# mainboard.net
KiCad netlist of a schematic drawn in EAGLE
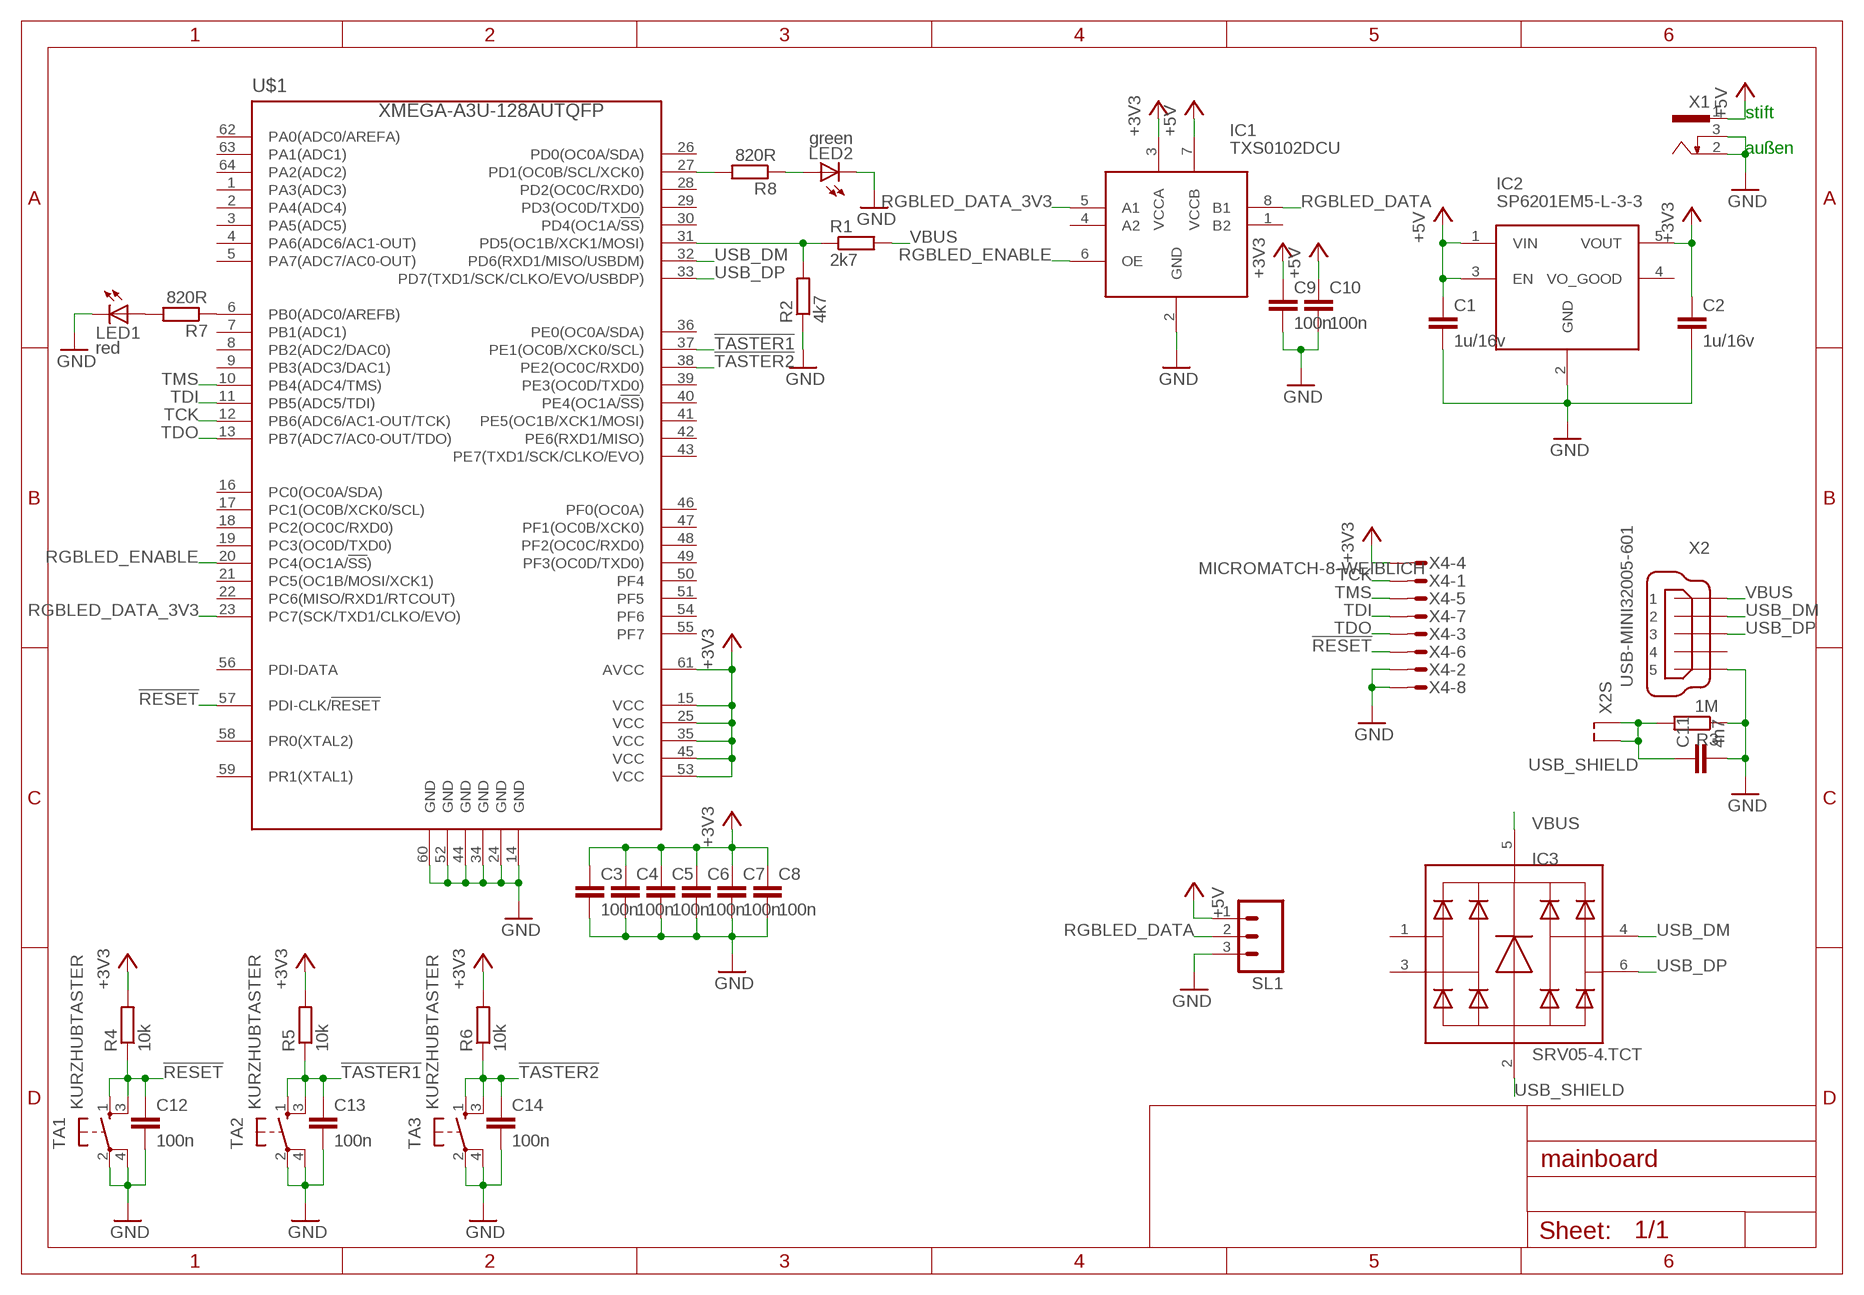
[diagram p0: schematic, sheet 1]

(export (version "E")
  (design (tool "Eeschema 10.0.6"))
  (components
    (comp (ref "C1")
      (value "1u/16v")
      (footprint "eagle-import:C0603")
      (libsource (lib "eagle-import") (part "C-EUC0603"))
    )
    (comp (ref "C2")
      (value "1u/16v")
      (footprint "eagle-import:C0603")
      (libsource (lib "eagle-import") (part "C-EUC0603"))
    )
    (comp (ref "C3")
      (value "100n")
      (footprint "eagle-import:C0603")
      (libsource (lib "eagle-import") (part "C-EUC0603"))
    )
    (comp (ref "C4")
      (value "100n")
      (footprint "eagle-import:C0603")
      (libsource (lib "eagle-import") (part "C-EUC0603"))
    )
    (comp (ref "C5")
      (value "100n")
      (footprint "eagle-import:C0603")
      (libsource (lib "eagle-import") (part "C-EUC0603"))
    )
    (comp (ref "C6")
      (value "100n")
      (footprint "eagle-import:C0603")
      (libsource (lib "eagle-import") (part "C-EUC0603"))
    )
    (comp (ref "C7")
      (value "100n")
      (footprint "eagle-import:C0603")
      (libsource (lib "eagle-import") (part "C-EUC0603"))
    )
    (comp (ref "C8")
      (value "100n")
      (footprint "eagle-import:C0603")
      (libsource (lib "eagle-import") (part "C-EUC0603"))
    )
    (comp (ref "C9")
      (value "100n")
      (footprint "eagle-import:C0603")
      (libsource (lib "eagle-import") (part "C-EUC0603"))
    )
    (comp (ref "C10")
      (value "100n")
      (footprint "eagle-import:C0603")
      (libsource (lib "eagle-import") (part "C-EUC0603"))
    )
    (comp (ref "C11")
      (value "4n7")
      (footprint "eagle-import:C0603")
      (libsource (lib "eagle-import") (part "C-EUC0603"))
    )
    (comp (ref "C12")
      (value "100n")
      (footprint "eagle-import:C0603")
      (libsource (lib "eagle-import") (part "C-EUC0603"))
    )
    (comp (ref "C13")
      (value "100n")
      (footprint "eagle-import:C0603")
      (libsource (lib "eagle-import") (part "C-EUC0603"))
    )
    (comp (ref "C14")
      (value "100n")
      (footprint "eagle-import:C0603")
      (libsource (lib "eagle-import") (part "C-EUC0603"))
    )
    (comp (ref "IC1")
      (value "TXS0102DCU")
      (footprint "eagle-import:DCU8")
      (libsource (lib "eagle-import") (part "TXS0102DCU"))
    )
    (comp (ref "IC2")
      (value "SP6201EM5-L-3-3")
      (footprint "eagle-import:SOT23-5")
      (libsource (lib "eagle-import") (part "SP6201EM5-L-3-3"))
    )
    (comp (ref "IC3")
      (value "SRV05-4.TCT")
      (footprint "eagle-import:SOT23-6")
      (libsource (lib "eagle-import") (part "SRV05-4.TCT"))
    )
    (comp (ref "LED1")
      (value "red")
      (footprint "eagle-import:CHIPLED_0603")
      (libsource (lib "eagle-import") (part "LEDCHIPLED_0603LR"))
    )
    (comp (ref "LED2")
      (value "green")
      (footprint "eagle-import:CHIPLED_0603")
      (libsource (lib "eagle-import") (part "LEDCHIPLED_0603LG"))
    )
    (comp (ref "R1")
      (value "2k7")
      (footprint "eagle-import:R0603")
      (libsource (lib "eagle-import") (part "R-EU_R0603"))
    )
    (comp (ref "R2")
      (value "4k7")
      (footprint "eagle-import:R0603")
      (libsource (lib "eagle-import") (part "R-EU_R0603"))
    )
    (comp (ref "R3")
      (value "1M")
      (footprint "eagle-import:R0603")
      (libsource (lib "eagle-import") (part "R-EU_R0603"))
    )
    (comp (ref "R4")
      (value "10k")
      (footprint "eagle-import:R0603")
      (libsource (lib "eagle-import") (part "R-EU_R0603"))
    )
    (comp (ref "R5")
      (value "10k")
      (footprint "eagle-import:R0603")
      (libsource (lib "eagle-import") (part "R-EU_R0603"))
    )
    (comp (ref "R6")
      (value "10k")
      (footprint "eagle-import:R0603")
      (libsource (lib "eagle-import") (part "R-EU_R0603"))
    )
    (comp (ref "R7")
      (value "820R")
      (footprint "eagle-import:R0603")
      (libsource (lib "eagle-import") (part "R-EU_R0603"))
    )
    (comp (ref "R8")
      (value "820R")
      (footprint "eagle-import:R0603")
      (libsource (lib "eagle-import") (part "R-EU_R0603"))
    )
    (comp (ref "SL1")
      (value "M03")
      (footprint "eagle-import:03P")
      (libsource (lib "eagle-import") (part "M03"))
    )
    (comp (ref "TA1")
      (value "KURZHUBTASTER")
      (footprint "eagle-import:TA93XX")
      (libsource (lib "eagle-import") (part "KURZHUBTASTER"))
    )
    (comp (ref "TA2")
      (value "KURZHUBTASTER")
      (footprint "eagle-import:TA93XX")
      (libsource (lib "eagle-import") (part "KURZHUBTASTER"))
    )
    (comp (ref "TA3")
      (value "KURZHUBTASTER")
      (footprint "eagle-import:TA93XX")
      (libsource (lib "eagle-import") (part "KURZHUBTASTER"))
    )
    (comp (ref "U$1")
      (value "XMEGA-A3U-128AUTQFP")
      (footprint "eagle-import:TQFP64")
      (libsource (lib "eagle-import") (part "XMEGA-A3UTQFP-128AU"))
    )
    (comp (ref "X1")
      (value "733980-62")
      (footprint "eagle-import:733980-62")
      (libsource (lib "eagle-import") (part "73398?0-62"))
    )
    (comp (ref "X2")
      (value "USB-MINI32005-601")
      (footprint "eagle-import:32005-601")
      (libsource (lib "eagle-import") (part "USB-MINI32005-601"))
    )
    (comp (ref "X4")
      (value "MICROMATCH-8-WEIBLICH")
      (footprint "eagle-import:MICROMATCH-8")
      (libsource (lib "eagle-import") (part "MICROMATCH-8-WEIBLICH"))
    )
  )
  (nets
    (net (code "1") (name "+3V3") (class "Default")
      (node (ref "C2") (pin "1") (pinfunction "1_1") (pintype "passive"))
      (node (ref "C3") (pin "1") (pinfunction "1_1") (pintype "passive"))
      (node (ref "C4") (pin "1") (pinfunction "1_1") (pintype "passive"))
      (node (ref "C5") (pin "1") (pinfunction "1_1") (pintype "passive"))
      (node (ref "C6") (pin "1") (pinfunction "1_1") (pintype "passive"))
      (node (ref "C7") (pin "1") (pinfunction "1_1") (pintype "passive"))
      (node (ref "C8") (pin "1") (pinfunction "1_1") (pintype "passive"))
      (node (ref "C9") (pin "1") (pinfunction "1_1") (pintype "passive"))
      (node (ref "IC1") (pin "3") (pinfunction "VCCA_3") (pintype "power_in"))
      (node (ref "IC2") (pin "5") (pinfunction "VOUT_5") (pintype "power_in"))
      (node (ref "R4") (pin "2") (pinfunction "2_2") (pintype "passive"))
      (node (ref "R5") (pin "2") (pinfunction "2_2") (pintype "passive"))
      (node (ref "R6") (pin "2") (pinfunction "2_2") (pintype "passive"))
      (node (ref "U$1") (pin "15") (pinfunction "VCC_15") (pintype "power_in"))
      (node (ref "U$1") (pin "25") (pinfunction "VCC_25") (pintype "power_in"))
      (node (ref "U$1") (pin "35") (pinfunction "VCC_35") (pintype "power_in"))
      (node (ref "U$1") (pin "45") (pinfunction "VCC_45") (pintype "power_in"))
      (node (ref "U$1") (pin "53") (pinfunction "VCC_53") (pintype "power_in"))
      (node (ref "U$1") (pin "61") (pinfunction "AVCC_61") (pintype "power_in"))
      (node (ref "X4") (pin "4") (pinfunction "S_4") (pintype "passive"))
    )
    (net (code "2") (name "+5V") (class "Default")
      (node (ref "C1") (pin "1") (pinfunction "1_1") (pintype "passive"))
      (node (ref "C10") (pin "1") (pinfunction "1_1") (pintype "passive"))
      (node (ref "IC1") (pin "7") (pinfunction "VCCB_7") (pintype "power_in"))
      (node (ref "IC2") (pin "1") (pinfunction "VIN_1") (pintype "power_in"))
      (node (ref "IC2") (pin "3") (pinfunction "EN_3") (pintype "input"))
      (node (ref "SL1") (pin "1") (pinfunction "1_1") (pintype "passive"))
      (node (ref "X1") (pin "1") (pinfunction "1_1") (pintype "passive"))
    )
    (net (code "3") (name "/RGBLED_DATA") (class "Default")
      (node (ref "IC1") (pin "8") (pinfunction "B1_8") (pintype "bidirectional"))
      (node (ref "SL1") (pin "2") (pinfunction "2_2") (pintype "passive"))
    )
    (net (code "4") (name "/RGBLED_DATA_3V3") (class "Default")
      (node (ref "IC1") (pin "5") (pinfunction "A1_5") (pintype "bidirectional"))
      (node (ref "U$1") (pin "23") (pinfunction "PC7(SCK/TXD1/CLKO/EVO)_23") (pintype "bidirectional"))
    )
    (net (code "5") (name "/RGBLED_ENABLE") (class "Default")
      (node (ref "IC1") (pin "6") (pinfunction "OE_6") (pintype "input"))
      (node (ref "U$1") (pin "20") (pinfunction "PC4(OC1A/~{SS})_20") (pintype "bidirectional"))
    )
    (net (code "6") (name "/TCK") (class "Default")
      (node (ref "U$1") (pin "12") (pinfunction "PB6(ADC6/AC1-OUT/TCK)_12") (pintype "bidirectional"))
      (node (ref "X4") (pin "1") (pinfunction "S_1") (pintype "passive"))
    )
    (net (code "7") (name "/TDI") (class "Default")
      (node (ref "U$1") (pin "11") (pinfunction "PB5(ADC5/TDI)_11") (pintype "bidirectional"))
      (node (ref "X4") (pin "7") (pinfunction "S_7") (pintype "passive"))
    )
    (net (code "8") (name "/TDO") (class "Default")
      (node (ref "U$1") (pin "13") (pinfunction "PB7(ADC7/AC0-OUT/TDO)_13") (pintype "bidirectional"))
      (node (ref "X4") (pin "3") (pinfunction "S_3") (pintype "passive"))
    )
    (net (code "9") (name "/TMS") (class "Default")
      (node (ref "U$1") (pin "10") (pinfunction "PB4(ADC4/TMS)_10") (pintype "bidirectional"))
      (node (ref "X4") (pin "5") (pinfunction "S_5") (pintype "passive"))
    )
    (net (code "10") (name "/USB_DM") (class "Default")
      (node (ref "IC3") (pin "4") (pinfunction "3_4") (pintype "passive"))
      (node (ref "U$1") (pin "32") (pinfunction "PD6(RXD1/MISO/USBDM)_32") (pintype "bidirectional"))
      (node (ref "X2") (pin "2") (pinfunction "2_2") (pintype "passive"))
    )
    (net (code "11") (name "/USB_DP") (class "Default")
      (node (ref "IC3") (pin "6") (pinfunction "4_6") (pintype "passive"))
      (node (ref "U$1") (pin "33") (pinfunction "PD7(TXD1/SCK/CLKO/EVO/USBDP)_33") (pintype "bidirectional"))
      (node (ref "X2") (pin "3") (pinfunction "3_3") (pintype "passive"))
    )
    (net (code "12") (name "/USB_SHIELD") (class "Default")
      (node (ref "C11") (pin "1") (pinfunction "1_1") (pintype "passive"))
      (node (ref "IC3") (pin "2") (pinfunction "A_2") (pintype "passive"))
      (node (ref "R3") (pin "2") (pinfunction "2_2") (pintype "passive"))
      (node (ref "X2") (pin "M1") (pinfunction "S1_M1") (pintype "passive"))
      (node (ref "X2") (pin "M2") (pinfunction "S2_M2") (pintype "passive"))
    )
    (net (code "13") (name "/VBUS") (class "Default")
      (node (ref "IC3") (pin "5") (pinfunction "K_5") (pintype "passive"))
      (node (ref "R1") (pin "2") (pinfunction "2_2") (pintype "passive"))
      (node (ref "X2") (pin "1") (pinfunction "1_1") (pintype "passive"))
    )
    (net (code "14") (name "/~{RESET}") (class "Default")
      (node (ref "C12") (pin "1") (pinfunction "1_1") (pintype "passive"))
      (node (ref "R4") (pin "1") (pinfunction "1_1") (pintype "passive"))
      (node (ref "TA1") (pin "1") (pinfunction "S_1") (pintype "passive"))
      (node (ref "TA1") (pin "3") (pinfunction "S1_3") (pintype "passive"))
      (node (ref "U$1") (pin "57") (pinfunction "PDI-CLK/~{RESET}_57") (pintype "input"))
      (node (ref "X4") (pin "6") (pinfunction "S_6") (pintype "passive"))
    )
    (net (code "15") (name "/~{TASTER1}") (class "Default")
      (node (ref "C13") (pin "1") (pinfunction "1_1") (pintype "passive"))
      (node (ref "R5") (pin "1") (pinfunction "1_1") (pintype "passive"))
      (node (ref "TA2") (pin "1") (pinfunction "S_1") (pintype "passive"))
      (node (ref "TA2") (pin "3") (pinfunction "S1_3") (pintype "passive"))
      (node (ref "U$1") (pin "37") (pinfunction "PE1(OC0B/XCK0/SCL)_37") (pintype "bidirectional"))
    )
    (net (code "16") (name "/~{TASTER2}") (class "Default")
      (node (ref "C14") (pin "1") (pinfunction "1_1") (pintype "passive"))
      (node (ref "R6") (pin "1") (pinfunction "1_1") (pintype "passive"))
      (node (ref "TA3") (pin "1") (pinfunction "S_1") (pintype "passive"))
      (node (ref "TA3") (pin "3") (pinfunction "S1_3") (pintype "passive"))
      (node (ref "U$1") (pin "38") (pinfunction "PE2(OC0C/RXD0)_38") (pintype "bidirectional"))
    )
    (net (code "17") (name "GND") (class "Default")
      (node (ref "C1") (pin "2") (pinfunction "2_2") (pintype "passive"))
      (node (ref "C10") (pin "2") (pinfunction "2_2") (pintype "passive"))
      (node (ref "C11") (pin "2") (pinfunction "2_2") (pintype "passive"))
      (node (ref "C12") (pin "2") (pinfunction "2_2") (pintype "passive"))
      (node (ref "C13") (pin "2") (pinfunction "2_2") (pintype "passive"))
      (node (ref "C14") (pin "2") (pinfunction "2_2") (pintype "passive"))
      (node (ref "C2") (pin "2") (pinfunction "2_2") (pintype "passive"))
      (node (ref "C3") (pin "2") (pinfunction "2_2") (pintype "passive"))
      (node (ref "C4") (pin "2") (pinfunction "2_2") (pintype "passive"))
      (node (ref "C5") (pin "2") (pinfunction "2_2") (pintype "passive"))
      (node (ref "C6") (pin "2") (pinfunction "2_2") (pintype "passive"))
      (node (ref "C7") (pin "2") (pinfunction "2_2") (pintype "passive"))
      (node (ref "C8") (pin "2") (pinfunction "2_2") (pintype "passive"))
      (node (ref "C9") (pin "2") (pinfunction "2_2") (pintype "passive"))
      (node (ref "IC1") (pin "2") (pinfunction "GND_2") (pintype "power_in"))
      (node (ref "IC2") (pin "2") (pinfunction "GND_2") (pintype "power_in"))
      (node (ref "LED1") (pin "C") (pinfunction "C_C") (pintype "passive"))
      (node (ref "LED2") (pin "C") (pinfunction "C_C") (pintype "passive"))
      (node (ref "R2") (pin "1") (pinfunction "1_1") (pintype "passive"))
      (node (ref "R3") (pin "1") (pinfunction "1_1") (pintype "passive"))
      (node (ref "SL1") (pin "3") (pinfunction "3_3") (pintype "passive"))
      (node (ref "TA1") (pin "2") (pinfunction "P_2") (pintype "passive"))
      (node (ref "TA1") (pin "4") (pinfunction "P1_4") (pintype "passive"))
      (node (ref "TA2") (pin "2") (pinfunction "P_2") (pintype "passive"))
      (node (ref "TA2") (pin "4") (pinfunction "P1_4") (pintype "passive"))
      (node (ref "TA3") (pin "2") (pinfunction "P_2") (pintype "passive"))
      (node (ref "TA3") (pin "4") (pinfunction "P1_4") (pintype "passive"))
      (node (ref "U$1") (pin "14") (pinfunction "GND_14") (pintype "power_in"))
      (node (ref "U$1") (pin "24") (pinfunction "GND_24") (pintype "power_in"))
      (node (ref "U$1") (pin "34") (pinfunction "GND_34") (pintype "power_in"))
      (node (ref "U$1") (pin "44") (pinfunction "GND_44") (pintype "power_in"))
      (node (ref "U$1") (pin "52") (pinfunction "GND_52") (pintype "power_in"))
      (node (ref "U$1") (pin "60") (pinfunction "GND_60") (pintype "power_in"))
      (node (ref "X1") (pin "2") (pinfunction "2_2") (pintype "passive"))
      (node (ref "X1") (pin "3") (pinfunction "3_3") (pintype "passive"))
      (node (ref "X2") (pin "5") (pinfunction "5_5") (pintype "passive"))
      (node (ref "X4") (pin "2") (pinfunction "S_2") (pintype "passive"))
      (node (ref "X4") (pin "8") (pinfunction "S_8") (pintype "passive"))
    )
    (net (code "18") (name "Net-(LED1-PadA)") (class "Default")
      (node (ref "LED1") (pin "A") (pinfunction "A_A") (pintype "passive"))
      (node (ref "R7") (pin "2") (pinfunction "2_2") (pintype "passive"))
    )
    (net (code "19") (name "Net-(LED2-PadA)") (class "Default")
      (node (ref "LED2") (pin "A") (pinfunction "A_A") (pintype "passive"))
      (node (ref "R8") (pin "1") (pinfunction "1_1") (pintype "passive"))
    )
    (net (code "20") (name "Net-(U$1-PB0(ADC0{slash}AREFB))") (class "Default")
      (node (ref "R7") (pin "1") (pinfunction "1_1") (pintype "passive"))
      (node (ref "U$1") (pin "6") (pinfunction "PB0(ADC0/AREFB)_6") (pintype "bidirectional"))
    )
    (net (code "21") (name "Net-(U$1-PD1(OC0B{slash}SCL{slash}XCK0))") (class "Default")
      (node (ref "R8") (pin "2") (pinfunction "2_2") (pintype "passive"))
      (node (ref "U$1") (pin "27") (pinfunction "PD1(OC0B/SCL/XCK0)_27") (pintype "bidirectional"))
    )
    (net (code "22") (name "Net-(U$1-PD5(OC1B{slash}XCK1{slash}MOSI))") (class "Default")
      (node (ref "R1") (pin "1") (pinfunction "1_1") (pintype "passive"))
      (node (ref "R2") (pin "2") (pinfunction "2_2") (pintype "passive"))
      (node (ref "U$1") (pin "31") (pinfunction "PD5(OC1B/XCK1/MOSI)_31") (pintype "bidirectional"))
    )
    (net (code "23") (name "unconnected-(IC1-A2-Pad4)") (class "Default")
      (node (ref "IC1") (pin "4") (pinfunction "A2_4") (pintype "bidirectional"))
    )
    (net (code "24") (name "unconnected-(IC1-B2-Pad1)") (class "Default")
      (node (ref "IC1") (pin "1") (pinfunction "B2_1") (pintype "bidirectional"))
    )
    (net (code "25") (name "unconnected-(IC2-VO_GOOD-Pad4)") (class "Default")
      (node (ref "IC2") (pin "4") (pinfunction "VO_GOOD_4") (pintype "output"))
    )
    (net (code "26") (name "unconnected-(IC3-2-Pad3)") (class "Default")
      (node (ref "IC3") (pin "3") (pinfunction "2_3") (pintype "passive"))
    )
    (net (code "27") (name "unconnected-(IC3-Pad1)") (class "Default")
      (node (ref "IC3") (pin "1") (pinfunction "1_1") (pintype "passive"))
    )
    (net (code "28") (name "unconnected-(U$1-PA0(ADC0{slash}AREFA)-Pad62)") (class "Default")
      (node (ref "U$1") (pin "62") (pinfunction "PA0(ADC0/AREFA)_62") (pintype "bidirectional"))
    )
    (net (code "29") (name "unconnected-(U$1-PA1(ADC1)-Pad63)") (class "Default")
      (node (ref "U$1") (pin "63") (pinfunction "PA1(ADC1)_63") (pintype "bidirectional"))
    )
    (net (code "30") (name "unconnected-(U$1-PA2(ADC2)-Pad64)") (class "Default")
      (node (ref "U$1") (pin "64") (pinfunction "PA2(ADC2)_64") (pintype "bidirectional"))
    )
    (net (code "31") (name "unconnected-(U$1-PA3(ADC3)-Pad1)") (class "Default")
      (node (ref "U$1") (pin "1") (pinfunction "PA3(ADC3)_1") (pintype "bidirectional"))
    )
    (net (code "32") (name "unconnected-(U$1-PA4(ADC4)-Pad2)") (class "Default")
      (node (ref "U$1") (pin "2") (pinfunction "PA4(ADC4)_2") (pintype "bidirectional"))
    )
    (net (code "33") (name "unconnected-(U$1-PA5(ADC5)-Pad3)") (class "Default")
      (node (ref "U$1") (pin "3") (pinfunction "PA5(ADC5)_3") (pintype "bidirectional"))
    )
    (net (code "34") (name "unconnected-(U$1-PA6(ADC6{slash}AC1-OUT)-Pad4)") (class "Default")
      (node (ref "U$1") (pin "4") (pinfunction "PA6(ADC6/AC1-OUT)_4") (pintype "bidirectional"))
    )
    (net (code "35") (name "unconnected-(U$1-PA7(ADC7{slash}AC0-OUT)-Pad5)") (class "Default")
      (node (ref "U$1") (pin "5") (pinfunction "PA7(ADC7/AC0-OUT)_5") (pintype "bidirectional"))
    )
    (net (code "36") (name "unconnected-(U$1-PB1(ADC1)-Pad7)") (class "Default")
      (node (ref "U$1") (pin "7") (pinfunction "PB1(ADC1)_7") (pintype "bidirectional"))
    )
    (net (code "37") (name "unconnected-(U$1-PB2(ADC2{slash}DAC0)-Pad8)") (class "Default")
      (node (ref "U$1") (pin "8") (pinfunction "PB2(ADC2/DAC0)_8") (pintype "bidirectional"))
    )
    (net (code "38") (name "unconnected-(U$1-PB3(ADC3{slash}DAC1)-Pad9)") (class "Default")
      (node (ref "U$1") (pin "9") (pinfunction "PB3(ADC3/DAC1)_9") (pintype "bidirectional"))
    )
    (net (code "39") (name "unconnected-(U$1-PC0(OC0A{slash}SDA)-Pad16)") (class "Default")
      (node (ref "U$1") (pin "16") (pinfunction "PC0(OC0A/SDA)_16") (pintype "bidirectional"))
    )
    (net (code "40") (name "unconnected-(U$1-PC1(OC0B{slash}XCK0{slash}SCL)-Pad17)") (class "Default")
      (node (ref "U$1") (pin "17") (pinfunction "PC1(OC0B/XCK0/SCL)_17") (pintype "bidirectional"))
    )
    (net (code "41") (name "unconnected-(U$1-PC2(OC0C{slash}RXD0)-Pad18)") (class "Default")
      (node (ref "U$1") (pin "18") (pinfunction "PC2(OC0C/RXD0)_18") (pintype "bidirectional"))
    )
    (net (code "42") (name "unconnected-(U$1-PC3(OC0D{slash}TXD0)-Pad19)") (class "Default")
      (node (ref "U$1") (pin "19") (pinfunction "PC3(OC0D/TXD0)_19") (pintype "bidirectional"))
    )
    (net (code "43") (name "unconnected-(U$1-PC5(OC1B{slash}MOSI{slash}XCK1)-Pad21)") (class "Default")
      (node (ref "U$1") (pin "21") (pinfunction "PC5(OC1B/MOSI/XCK1)_21") (pintype "bidirectional"))
    )
    (net (code "44") (name "unconnected-(U$1-PC6(MISO{slash}RXD1{slash}RTCOUT)-Pad22)") (class "Default")
      (node (ref "U$1") (pin "22") (pinfunction "PC6(MISO/RXD1/RTCOUT)_22") (pintype "bidirectional"))
    )
    (net (code "45") (name "unconnected-(U$1-PD0(OC0A{slash}SDA)-Pad26)") (class "Default")
      (node (ref "U$1") (pin "26") (pinfunction "PD0(OC0A/SDA)_26") (pintype "bidirectional"))
    )
    (net (code "46") (name "unconnected-(U$1-PD2(OC0C{slash}RXD0)-Pad28)") (class "Default")
      (node (ref "U$1") (pin "28") (pinfunction "PD2(OC0C/RXD0)_28") (pintype "bidirectional"))
    )
    (net (code "47") (name "unconnected-(U$1-PD3(OC0D{slash}TXD0)-Pad29)") (class "Default")
      (node (ref "U$1") (pin "29") (pinfunction "PD3(OC0D/TXD0)_29") (pintype "bidirectional"))
    )
    (net (code "48") (name "unconnected-(U$1-PD4(OC1A{slash}~{SS})-Pad30)") (class "Default")
      (node (ref "U$1") (pin "30") (pinfunction "PD4(OC1A/~{SS})_30") (pintype "bidirectional"))
    )
    (net (code "49") (name "unconnected-(U$1-PDI-DATA-Pad56)") (class "Default")
      (node (ref "U$1") (pin "56") (pinfunction "PDI-DATA_56") (pintype "bidirectional"))
    )
    (net (code "50") (name "unconnected-(U$1-PE0(OC0A{slash}SDA)-Pad36)") (class "Default")
      (node (ref "U$1") (pin "36") (pinfunction "PE0(OC0A/SDA)_36") (pintype "bidirectional"))
    )
    (net (code "51") (name "unconnected-(U$1-PE3(OC0D{slash}TXD0)-Pad39)") (class "Default")
      (node (ref "U$1") (pin "39") (pinfunction "PE3(OC0D/TXD0)_39") (pintype "bidirectional"))
    )
    (net (code "52") (name "unconnected-(U$1-PE4(OC1A{slash}~{SS})-Pad40)") (class "Default")
      (node (ref "U$1") (pin "40") (pinfunction "PE4(OC1A/~{SS})_40") (pintype "bidirectional"))
    )
    (net (code "53") (name "unconnected-(U$1-PE5(OC1B{slash}XCK1{slash}MOSI)-Pad41)") (class "Default")
      (node (ref "U$1") (pin "41") (pinfunction "PE5(OC1B/XCK1/MOSI)_41") (pintype "bidirectional"))
    )
    (net (code "54") (name "unconnected-(U$1-PE6(RXD1{slash}MISO)-Pad42)") (class "Default")
      (node (ref "U$1") (pin "42") (pinfunction "PE6(RXD1/MISO)_42") (pintype "bidirectional"))
    )
    (net (code "55") (name "unconnected-(U$1-PE7(TXD1{slash}SCK{slash}CLKO{slash}EVO)-Pad43)") (class "Default")
      (node (ref "U$1") (pin "43") (pinfunction "PE7(TXD1/SCK/CLKO/EVO)_43") (pintype "bidirectional"))
    )
    (net (code "56") (name "unconnected-(U$1-PF0(OC0A)-Pad46)") (class "Default")
      (node (ref "U$1") (pin "46") (pinfunction "PF0(OC0A)_46") (pintype "bidirectional"))
    )
    (net (code "57") (name "unconnected-(U$1-PF1(OC0B{slash}XCK0)-Pad47)") (class "Default")
      (node (ref "U$1") (pin "47") (pinfunction "PF1(OC0B/XCK0)_47") (pintype "bidirectional"))
    )
    (net (code "58") (name "unconnected-(U$1-PF2(OC0C{slash}RXD0)-Pad48)") (class "Default")
      (node (ref "U$1") (pin "48") (pinfunction "PF2(OC0C/RXD0)_48") (pintype "bidirectional"))
    )
    (net (code "59") (name "unconnected-(U$1-PF3(OC0D{slash}TXD0)-Pad49)") (class "Default")
      (node (ref "U$1") (pin "49") (pinfunction "PF3(OC0D/TXD0)_49") (pintype "bidirectional"))
    )
    (net (code "60") (name "unconnected-(U$1-PF4-Pad50)") (class "Default")
      (node (ref "U$1") (pin "50") (pinfunction "PF4_50") (pintype "bidirectional"))
    )
    (net (code "61") (name "unconnected-(U$1-PF5-Pad51)") (class "Default")
      (node (ref "U$1") (pin "51") (pinfunction "PF5_51") (pintype "bidirectional"))
    )
    (net (code "62") (name "unconnected-(U$1-PF6-Pad54)") (class "Default")
      (node (ref "U$1") (pin "54") (pinfunction "PF6_54") (pintype "bidirectional"))
    )
    (net (code "63") (name "unconnected-(U$1-PF7-Pad55)") (class "Default")
      (node (ref "U$1") (pin "55") (pinfunction "PF7_55") (pintype "bidirectional"))
    )
    (net (code "64") (name "unconnected-(U$1-PR0(XTAL2)-Pad58)") (class "Default")
      (node (ref "U$1") (pin "58") (pinfunction "PR0(XTAL2)_58") (pintype "bidirectional"))
    )
    (net (code "65") (name "unconnected-(U$1-PR1(XTAL1)-Pad59)") (class "Default")
      (node (ref "U$1") (pin "59") (pinfunction "PR1(XTAL1)_59") (pintype "bidirectional"))
    )
    (net (code "66") (name "unconnected-(X2-Pad4)") (class "Default")
      (node (ref "X2") (pin "4") (pinfunction "4_4") (pintype "passive"))
    )
  )
)
